# MCU.net
KiCad netlist of a schematic drawn in Altium Designer
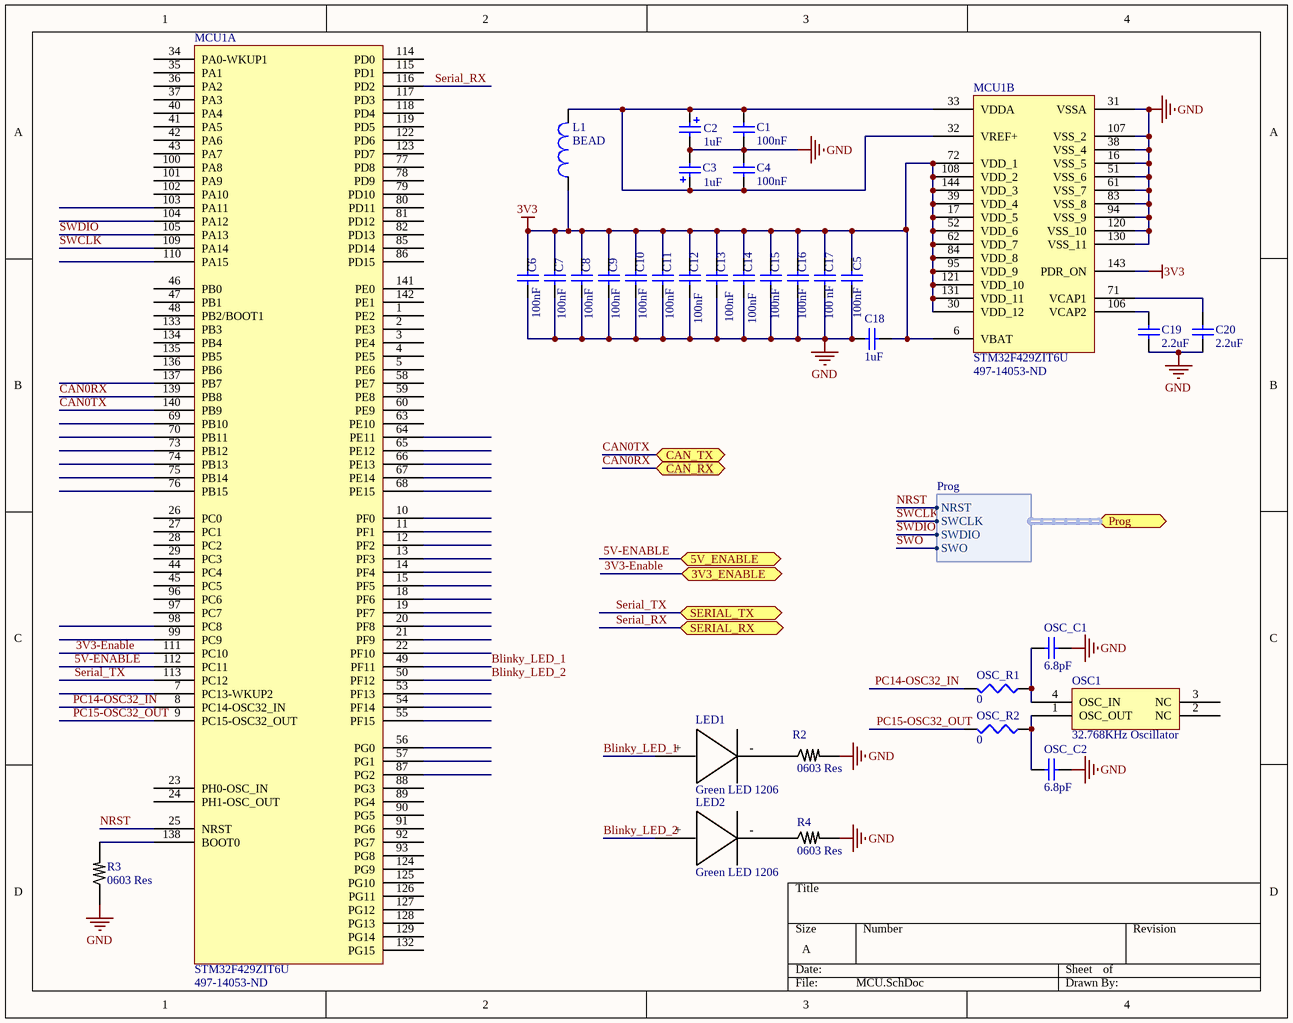
[diagram p0: MCU.SchDoc]

(export (version "E")
  (design (tool "Eeschema 10.0.6"))
  (components
    (comp (ref "C1")
      (value "100nF")
      (footprint "SMD0603")
      (description "Ceramic Chip Capacitor")
      (fields (field (name "Comment") "Cap"))
      (libsource (lib "Components") (part "Capacitor Ceramic"))
    )
    (comp (ref "C2")
      (value "1uF")
      (footprint "SMD1206 Polarized")
      (description "Polarized Capacitor (Surface Mount)")
      (fields (field (name "Comment") "Cap"))
      (libsource (lib "Components") (part "Capacitor Polarized"))
    )
    (comp (ref "C3")
      (value "1uF")
      (footprint "SMD1206 Polarized")
      (description "Polarized Capacitor (Surface Mount)")
      (fields (field (name "Comment") "Cap"))
      (libsource (lib "Components") (part "Capacitor Polarized"))
    )
    (comp (ref "C4")
      (value "100nF")
      (footprint "SMD0603")
      (description "Ceramic Chip Capacitor")
      (fields (field (name "Comment") "Cap"))
      (libsource (lib "Components") (part "Capacitor Ceramic"))
    )
    (comp (ref "C5")
      (value "100nF")
      (footprint "SMD0603")
      (description "Ceramic Chip Capacitor")
      (fields (field (name "Comment") "Cap"))
      (libsource (lib "Components") (part "Capacitor Ceramic"))
    )
    (comp (ref "C6")
      (value "100nF")
      (footprint "SMD0603")
      (description "Ceramic Chip Capacitor")
      (fields (field (name "Comment") "Cap"))
      (libsource (lib "Components") (part "Capacitor Ceramic"))
    )
    (comp (ref "C7")
      (value "100nF")
      (footprint "SMD0603")
      (description "Ceramic Chip Capacitor")
      (fields (field (name "Comment") "Cap"))
      (libsource (lib "Components") (part "Capacitor Ceramic"))
    )
    (comp (ref "C8")
      (value "100nF")
      (footprint "SMD0603")
      (description "Ceramic Chip Capacitor")
      (fields (field (name "Comment") "Cap"))
      (libsource (lib "Components") (part "Capacitor Ceramic"))
    )
    (comp (ref "C9")
      (value "100nF")
      (footprint "SMD0603")
      (description "Ceramic Chip Capacitor")
      (fields (field (name "Comment") "Cap"))
      (libsource (lib "Components") (part "Capacitor Ceramic"))
    )
    (comp (ref "C10")
      (value "100nF")
      (footprint "SMD0603")
      (description "Ceramic Chip Capacitor")
      (fields (field (name "Comment") "Cap"))
      (libsource (lib "Components") (part "Capacitor Ceramic"))
    )
    (comp (ref "C11")
      (value "100nF")
      (footprint "SMD0603")
      (description "Ceramic Chip Capacitor")
      (fields (field (name "Comment") "Cap"))
      (libsource (lib "Components") (part "Capacitor Ceramic"))
    )
    (comp (ref "C12")
      (value "100nF")
      (footprint "SMD0603")
      (description "Ceramic Chip Capacitor")
      (fields (field (name "Comment") "Cap"))
      (libsource (lib "Components") (part "Capacitor Ceramic"))
    )
    (comp (ref "C13")
      (value "100nF")
      (footprint "SMD0603")
      (description "Ceramic Chip Capacitor")
      (fields (field (name "Comment") "Cap"))
      (libsource (lib "Components") (part "Capacitor Ceramic"))
    )
    (comp (ref "C14")
      (value "100nF")
      (footprint "SMD0603")
      (description "Ceramic Chip Capacitor")
      (fields (field (name "Comment") "Cap"))
      (libsource (lib "Components") (part "Capacitor Ceramic"))
    )
    (comp (ref "C15")
      (value "100nF")
      (footprint "SMD0603")
      (description "Ceramic Chip Capacitor")
      (fields (field (name "Comment") "Cap"))
      (libsource (lib "Components") (part "Capacitor Ceramic"))
    )
    (comp (ref "C16")
      (value "100nF")
      (footprint "SMD0603")
      (description "Ceramic Chip Capacitor")
      (fields (field (name "Comment") "Cap"))
      (libsource (lib "Components") (part "Capacitor Ceramic"))
    )
    (comp (ref "C17")
      (value "100 nF")
      (footprint "SMD0603")
      (description "Ceramic Chip Capacitor")
      (fields (field (name "Comment") "Cap"))
      (libsource (lib "Components") (part "Capacitor Ceramic"))
    )
    (comp (ref "C18")
      (value "1uF")
      (footprint "SMD0603")
      (description "Ceramic Chip Capacitor")
      (fields (field (name "Comment") "Cap"))
      (libsource (lib "Components") (part "Capacitor Ceramic"))
    )
    (comp (ref "C19")
      (value "2.2uF")
      (footprint "SMD1206")
      (description "Ceramic Chip Capacitor")
      (fields (field (name "Comment") "Cap"))
      (libsource (lib "Components") (part "Capacitor Ceramic"))
    )
    (comp (ref "C20")
      (value "2.2uF")
      (footprint "SMD1206")
      (description "Ceramic Chip Capacitor")
      (fields (field (name "Comment") "Cap"))
      (libsource (lib "Components") (part "Capacitor Ceramic"))
    )
    (comp (ref "L1")
      (value "BEAD")
      (footprint "SMD0603")
      (description "Ferrite Bead")
      (fields (field (name "PART") "BK1608HS601-TV"))
      (libsource (lib "Components") (part "Chip Ferrite Bead"))
    )
    (comp (ref "LED1")
      (value "Green LED 1206")
      (footprint "Panel_Mount_LED")
      (description "Green surface mount LED")
      (libsource (lib "CUBAJA") (part "1206 Green LED"))
    )
    (comp (ref "LED2")
      (value "Green LED 1206")
      (footprint "Panel_Mount_LED")
      (description "Green surface mount LED")
      (libsource (lib "CUBAJA") (part "1206 Green LED"))
    )
    (comp (ref "MCU1")
      (value "STM32F429ZIT6U")
      (footprint "LQPF144")
      (fields (field (name "SUPPLIER PART NUMBER 1") "497-14053-ND"))
      (libsource (lib "Components") (part "STM32F429ZIT6U"))
    )
    (comp (ref "OSC1")
      (value "32.768KHz Oscillator")
      (footprint "MC-306-OSC")
      (description "32.7680kHz Oscillator")
      (libsource (lib "Components") (part "MC-306 32.768K-E3"))
    )
    (comp (ref "OSC_C1")
      (value "6.8pF")
      (footprint "SMD0603")
      (description "Ceramic Chip Capacitor")
      (fields (field (name "Comment") "Cap"))
      (libsource (lib "Components") (part "Capacitor Ceramic"))
    )
    (comp (ref "OSC_C2")
      (value "6.8pF")
      (footprint "SMD0603")
      (description "Ceramic Chip Capacitor")
      (fields (field (name "Comment") "Cap"))
      (libsource (lib "Components") (part "Capacitor Ceramic"))
    )
    (comp (ref "OSC_R1")
      (value "0")
      (footprint "SMD0603")
      (description "Resistor")
      (fields (field (name "Comment") "Res"))
      (libsource (lib "Components") (part "Resistor"))
    )
    (comp (ref "OSC_R2")
      (value "0")
      (footprint "SMD0603")
      (description "Resistor")
      (fields (field (name "Comment") "Res"))
      (libsource (lib "Components") (part "Resistor"))
    )
    (comp (ref "R2")
      (value "0603 Res")
      (footprint "0603/1608 SMD Resistor")
      (libsource (lib "CornellBajaLibrary") (part "0603 Res"))
    )
    (comp (ref "R3")
      (value "0603 Res")
      (footprint "0603/1608 SMD Resistor")
      (libsource (lib "CornellBajaLibrary") (part "0603 Res"))
    )
    (comp (ref "R4")
      (value "0603 Res")
      (footprint "0603/1608 SMD Resistor")
      (libsource (lib "CornellBajaLibrary") (part "0603 Res"))
    )
  )
  (nets
    (net (code "2") (name "/3V3-Enable") (class "Default")
      (node (ref "MCU1") (pin "111") (pinfunction "PC10_111") (pintype "passive"))
    )
    (net (code "3") (name "/5V-ENABLE") (class "Default")
      (node (ref "MCU1") (pin "112") (pinfunction "PC11_112") (pintype "passive"))
    )
    (net (code "4") (name "/Blinky_LED_1") (class "Default")
      (node (ref "LED1") (pin "+") (pintype "passive"))
      (node (ref "MCU1") (pin "49") (pinfunction "PF11_49") (pintype "passive"))
    )
    (net (code "5") (name "/Blinky_LED_2") (class "Default")
      (node (ref "LED2") (pin "+") (pintype "passive"))
      (node (ref "MCU1") (pin "50") (pinfunction "PF12_50") (pintype "passive"))
    )
    (net (code "6") (name "/CAN0RX") (class "Default")
      (node (ref "MCU1") (pin "139") (pinfunction "PB8_139") (pintype "passive"))
    )
    (net (code "7") (name "/CAN0TX") (class "Default")
      (node (ref "MCU1") (pin "140") (pinfunction "PB9_140") (pintype "passive"))
    )
    (net (code "8") (name "/NRST") (class "Default")
      (node (ref "MCU1") (pin "25") (pinfunction "NRST_25") (pintype "passive"))
    )
    (net (code "9") (name "/PC14-OSC32_IN") (class "Default")
      (node (ref "MCU1") (pin "8") (pinfunction "PC14-OSC32_IN_8") (pintype "passive"))
      (node (ref "OSC_R1") (pin "2") (pinfunction "2_2") (pintype "passive"))
    )
    (net (code "10") (name "/PC15-OSC32_OUT") (class "Default")
      (node (ref "MCU1") (pin "9") (pinfunction "PC15-OSC32_OUT_9") (pintype "passive"))
      (node (ref "OSC_R2") (pin "2") (pinfunction "2_2") (pintype "passive"))
    )
    (net (code "11") (name "/SWCLK") (class "Default")
      (node (ref "MCU1") (pin "109") (pinfunction "PA14_109") (pintype "passive"))
    )
    (net (code "12") (name "/SWDIO") (class "Default")
      (node (ref "MCU1") (pin "105") (pinfunction "PA13_105") (pintype "passive"))
    )
    (net (code "14") (name "/Serial_RX") (class "Default")
      (node (ref "MCU1") (pin "116") (pinfunction "PD2_116") (pintype "passive"))
    )
    (net (code "15") (name "/Serial_TX") (class "Default")
      (node (ref "MCU1") (pin "113") (pinfunction "PC12_113") (pintype "passive"))
    )
    (net (code "17") (name "3V3") (class "Default")
      (node (ref "C10") (pin "2") (pinfunction "2_2") (pintype "passive"))
      (node (ref "C11") (pin "2") (pinfunction "2_2") (pintype "passive"))
      (node (ref "C12") (pin "2") (pinfunction "2_2") (pintype "passive"))
      (node (ref "C13") (pin "2") (pinfunction "2_2") (pintype "passive"))
      (node (ref "C14") (pin "2") (pinfunction "2_2") (pintype "passive"))
      (node (ref "C15") (pin "2") (pinfunction "2_2") (pintype "passive"))
      (node (ref "C16") (pin "2") (pinfunction "2_2") (pintype "passive"))
      (node (ref "C17") (pin "2") (pinfunction "2_2") (pintype "passive"))
      (node (ref "C18") (pin "1") (pinfunction "1_1") (pintype "passive"))
      (node (ref "C5") (pin "1") (pinfunction "1_1") (pintype "passive"))
      (node (ref "C6") (pin "2") (pinfunction "2_2") (pintype "passive"))
      (node (ref "C7") (pin "2") (pinfunction "2_2") (pintype "passive"))
      (node (ref "C8") (pin "2") (pinfunction "2_2") (pintype "passive"))
      (node (ref "C9") (pin "2") (pinfunction "2_2") (pintype "passive"))
      (node (ref "L1") (pin "1") (pintype "passive"))
      (node (ref "MCU1") (pin "108") (pinfunction "VDD_2_108") (pintype "passive"))
      (node (ref "MCU1") (pin "121") (pinfunction "VDD_10_121") (pintype "passive"))
      (node (ref "MCU1") (pin "131") (pinfunction "VDD_11_131") (pintype "passive"))
      (node (ref "MCU1") (pin "143") (pinfunction "PDR_ON_143") (pintype "passive"))
      (node (ref "MCU1") (pin "144") (pinfunction "VDD_3_144") (pintype "passive"))
      (node (ref "MCU1") (pin "17") (pinfunction "VDD_5_17") (pintype "passive"))
      (node (ref "MCU1") (pin "30") (pinfunction "VDD_12_30") (pintype "passive"))
      (node (ref "MCU1") (pin "39") (pinfunction "VDD_4_39") (pintype "passive"))
      (node (ref "MCU1") (pin "52") (pinfunction "VDD_6_52") (pintype "passive"))
      (node (ref "MCU1") (pin "6") (pinfunction "VBAT_6") (pintype "passive"))
      (node (ref "MCU1") (pin "62") (pinfunction "VDD_7_62") (pintype "passive"))
      (node (ref "MCU1") (pin "72") (pinfunction "VDD_1_72") (pintype "passive"))
      (node (ref "MCU1") (pin "84") (pinfunction "VDD_8_84") (pintype "passive"))
      (node (ref "MCU1") (pin "95") (pinfunction "VDD_9_95") (pintype "passive"))
    )
    (net (code "18") (name "GND") (class "Default")
      (node (ref "C1") (pin "1") (pinfunction "1_1") (pintype "passive"))
      (node (ref "C10") (pin "1") (pinfunction "1_1") (pintype "passive"))
      (node (ref "C11") (pin "1") (pinfunction "1_1") (pintype "passive"))
      (node (ref "C12") (pin "1") (pinfunction "1_1") (pintype "passive"))
      (node (ref "C13") (pin "1") (pinfunction "1_1") (pintype "passive"))
      (node (ref "C14") (pin "1") (pinfunction "1_1") (pintype "passive"))
      (node (ref "C15") (pin "1") (pinfunction "1_1") (pintype "passive"))
      (node (ref "C16") (pin "1") (pinfunction "1_1") (pintype "passive"))
      (node (ref "C17") (pin "1") (pinfunction "1_1") (pintype "passive"))
      (node (ref "C18") (pin "2") (pinfunction "2_2") (pintype "passive"))
      (node (ref "C19") (pin "1") (pinfunction "1_1") (pintype "passive"))
      (node (ref "C2") (pin "2") (pinfunction "2_2") (pintype "passive"))
      (node (ref "C20") (pin "1") (pinfunction "1_1") (pintype "passive"))
      (node (ref "C3") (pin "2") (pinfunction "2_2") (pintype "passive"))
      (node (ref "C4") (pin "2") (pinfunction "2_2") (pintype "passive"))
      (node (ref "C5") (pin "2") (pinfunction "2_2") (pintype "passive"))
      (node (ref "C6") (pin "1") (pinfunction "1_1") (pintype "passive"))
      (node (ref "C7") (pin "1") (pinfunction "1_1") (pintype "passive"))
      (node (ref "C8") (pin "1") (pinfunction "1_1") (pintype "passive"))
      (node (ref "C9") (pin "1") (pinfunction "1_1") (pintype "passive"))
      (node (ref "MCU1") (pin "107") (pinfunction "VSS_2_107") (pintype "passive"))
      (node (ref "MCU1") (pin "120") (pinfunction "VSS_10_120") (pintype "passive"))
      (node (ref "MCU1") (pin "130") (pinfunction "VSS_11_130") (pintype "passive"))
      (node (ref "MCU1") (pin "16") (pinfunction "VSS_5_16") (pintype "passive"))
      (node (ref "MCU1") (pin "31") (pinfunction "VSSA_31") (pintype "passive"))
      (node (ref "MCU1") (pin "38") (pinfunction "VSS_4_38") (pintype "passive"))
      (node (ref "MCU1") (pin "51") (pinfunction "VSS_6_51") (pintype "passive"))
      (node (ref "MCU1") (pin "61") (pinfunction "VSS_7_61") (pintype "passive"))
      (node (ref "MCU1") (pin "83") (pinfunction "VSS_8_83") (pintype "passive"))
      (node (ref "MCU1") (pin "94") (pinfunction "VSS_9_94") (pintype "passive"))
      (node (ref "OSC_C1") (pin "1") (pinfunction "1_1") (pintype "passive"))
      (node (ref "OSC_C2") (pin "1") (pinfunction "1_1") (pintype "passive"))
      (node (ref "R2") (pin "2") (pinfunction "2_2") (pintype "passive"))
      (node (ref "R3") (pin "1") (pinfunction "1_1") (pintype "passive"))
      (node (ref "R4") (pin "2") (pinfunction "2_2") (pintype "passive"))
    )
    (net (code "19") (name "Net-(LED1-Pad-)") (class "Default")
      (node (ref "LED1") (pin "-") (pintype "passive"))
      (node (ref "R2") (pin "1") (pinfunction "1_1") (pintype "passive"))
    )
    (net (code "20") (name "Net-(LED2-Pad-)") (class "Default")
      (node (ref "LED2") (pin "-") (pintype "passive"))
      (node (ref "R4") (pin "1") (pinfunction "1_1") (pintype "passive"))
    )
    (net (code "21") (name "Net-(MCU1A-BOOT0)") (class "Default")
      (node (ref "MCU1") (pin "138") (pinfunction "BOOT0_138") (pintype "passive"))
      (node (ref "R3") (pin "2") (pinfunction "2_2") (pintype "passive"))
    )
    (net (code "22") (name "Net-(MCU1B-VCAP1)") (class "Default")
      (node (ref "C20") (pin "2") (pinfunction "2_2") (pintype "passive"))
      (node (ref "MCU1") (pin "71") (pinfunction "VCAP1_71") (pintype "passive"))
    )
    (net (code "23") (name "Net-(MCU1B-VCAP2)") (class "Default")
      (node (ref "C19") (pin "2") (pinfunction "2_2") (pintype "passive"))
      (node (ref "MCU1") (pin "106") (pinfunction "VCAP2_106") (pintype "passive"))
    )
    (net (code "24") (name "Net-(MCU1B-VDDA)") (class "Default")
      (node (ref "C1") (pin "2") (pinfunction "2_2") (pintype "passive"))
      (node (ref "C2") (pin "1") (pinfunction "1_1") (pintype "passive"))
      (node (ref "C3") (pin "1") (pinfunction "1_1") (pintype "passive"))
      (node (ref "C4") (pin "1") (pinfunction "1_1") (pintype "passive"))
      (node (ref "L1") (pin "2") (pintype "passive"))
      (node (ref "MCU1") (pin "32") (pinfunction "VREF+_32") (pintype "passive"))
      (node (ref "MCU1") (pin "33") (pinfunction "VDDA_33") (pintype "passive"))
    )
    (net (code "25") (name "Net-(OSC1-OSC_IN)") (class "Default")
      (node (ref "OSC1") (pin "4") (pinfunction "OSC_IN_4") (pintype "passive"))
      (node (ref "OSC_C1") (pin "2") (pinfunction "2_2") (pintype "passive"))
      (node (ref "OSC_R1") (pin "1") (pinfunction "1_1") (pintype "passive"))
    )
    (net (code "26") (name "Net-(OSC1-OSC_OUT)") (class "Default")
      (node (ref "OSC1") (pin "1") (pinfunction "OSC_OUT_1") (pintype "passive"))
      (node (ref "OSC_C2") (pin "2") (pinfunction "2_2") (pintype "passive"))
      (node (ref "OSC_R2") (pin "1") (pinfunction "1_1") (pintype "passive"))
    )
    (net (code "27") (name "unconnected-(MCU1A-PA0-WKUP1-Pad34)") (class "Default")
      (node (ref "MCU1") (pin "34") (pinfunction "PA0-WKUP1_34") (pintype "passive"))
    )
    (net (code "28") (name "unconnected-(MCU1A-PA1-Pad35)") (class "Default")
      (node (ref "MCU1") (pin "35") (pinfunction "PA1_35") (pintype "passive"))
    )
    (net (code "29") (name "unconnected-(MCU1A-PA2-Pad36)") (class "Default")
      (node (ref "MCU1") (pin "36") (pinfunction "PA2_36") (pintype "passive"))
    )
    (net (code "30") (name "unconnected-(MCU1A-PA3-Pad37)") (class "Default")
      (node (ref "MCU1") (pin "37") (pinfunction "PA3_37") (pintype "passive"))
    )
    (net (code "31") (name "unconnected-(MCU1A-PA4-Pad40)") (class "Default")
      (node (ref "MCU1") (pin "40") (pinfunction "PA4_40") (pintype "passive"))
    )
    (net (code "32") (name "unconnected-(MCU1A-PA5-Pad41)") (class "Default")
      (node (ref "MCU1") (pin "41") (pinfunction "PA5_41") (pintype "passive"))
    )
    (net (code "33") (name "unconnected-(MCU1A-PA6-Pad42)") (class "Default")
      (node (ref "MCU1") (pin "42") (pinfunction "PA6_42") (pintype "passive"))
    )
    (net (code "34") (name "unconnected-(MCU1A-PA7-Pad43)") (class "Default")
      (node (ref "MCU1") (pin "43") (pinfunction "PA7_43") (pintype "passive"))
    )
    (net (code "35") (name "unconnected-(MCU1A-PA8-Pad100)") (class "Default")
      (node (ref "MCU1") (pin "100") (pinfunction "PA8_100") (pintype "passive"))
    )
    (net (code "36") (name "unconnected-(MCU1A-PA9-Pad101)") (class "Default")
      (node (ref "MCU1") (pin "101") (pinfunction "PA9_101") (pintype "passive"))
    )
    (net (code "37") (name "unconnected-(MCU1A-PA10-Pad102)") (class "Default")
      (node (ref "MCU1") (pin "102") (pinfunction "PA10_102") (pintype "passive"))
    )
    (net (code "38") (name "unconnected-(MCU1A-PA11-Pad103)") (class "Default")
      (node (ref "MCU1") (pin "103") (pinfunction "PA11_103") (pintype "passive"))
    )
    (net (code "39") (name "unconnected-(MCU1A-PA12-Pad104)") (class "Default")
      (node (ref "MCU1") (pin "104") (pinfunction "PA12_104") (pintype "passive"))
    )
    (net (code "40") (name "unconnected-(MCU1A-PA15-Pad110)") (class "Default")
      (node (ref "MCU1") (pin "110") (pinfunction "PA15_110") (pintype "passive"))
    )
    (net (code "41") (name "unconnected-(MCU1A-PB0-Pad46)") (class "Default")
      (node (ref "MCU1") (pin "46") (pinfunction "PB0_46") (pintype "passive"))
    )
    (net (code "42") (name "unconnected-(MCU1A-PB1-Pad47)") (class "Default")
      (node (ref "MCU1") (pin "47") (pinfunction "PB1_47") (pintype "passive"))
    )
    (net (code "43") (name "unconnected-(MCU1A-PB2{slash}BOOT1-Pad48)") (class "Default")
      (node (ref "MCU1") (pin "48") (pinfunction "PB2/BOOT1_48") (pintype "passive"))
    )
    (net (code "44") (name "unconnected-(MCU1A-PB3-Pad133)") (class "Default")
      (node (ref "MCU1") (pin "133") (pinfunction "PB3_133") (pintype "passive"))
    )
    (net (code "45") (name "unconnected-(MCU1A-PB4-Pad134)") (class "Default")
      (node (ref "MCU1") (pin "134") (pinfunction "PB4_134") (pintype "passive"))
    )
    (net (code "46") (name "unconnected-(MCU1A-PB5-Pad135)") (class "Default")
      (node (ref "MCU1") (pin "135") (pinfunction "PB5_135") (pintype "passive"))
    )
    (net (code "47") (name "unconnected-(MCU1A-PB6-Pad136)") (class "Default")
      (node (ref "MCU1") (pin "136") (pinfunction "PB6_136") (pintype "passive"))
    )
    (net (code "48") (name "unconnected-(MCU1A-PB7-Pad137)") (class "Default")
      (node (ref "MCU1") (pin "137") (pinfunction "PB7_137") (pintype "passive"))
    )
    (net (code "49") (name "unconnected-(MCU1A-PB10-Pad69)") (class "Default")
      (node (ref "MCU1") (pin "69") (pinfunction "PB10_69") (pintype "passive"))
    )
    (net (code "50") (name "unconnected-(MCU1A-PB11-Pad70)") (class "Default")
      (node (ref "MCU1") (pin "70") (pinfunction "PB11_70") (pintype "passive"))
    )
    (net (code "51") (name "unconnected-(MCU1A-PB12-Pad73)") (class "Default")
      (node (ref "MCU1") (pin "73") (pinfunction "PB12_73") (pintype "passive"))
    )
    (net (code "52") (name "unconnected-(MCU1A-PB13-Pad74)") (class "Default")
      (node (ref "MCU1") (pin "74") (pinfunction "PB13_74") (pintype "passive"))
    )
    (net (code "53") (name "unconnected-(MCU1A-PB14-Pad75)") (class "Default")
      (node (ref "MCU1") (pin "75") (pinfunction "PB14_75") (pintype "passive"))
    )
    (net (code "54") (name "unconnected-(MCU1A-PB15-Pad76)") (class "Default")
      (node (ref "MCU1") (pin "76") (pinfunction "PB15_76") (pintype "passive"))
    )
    (net (code "55") (name "unconnected-(MCU1A-PC0-Pad26)") (class "Default")
      (node (ref "MCU1") (pin "26") (pinfunction "PC0_26") (pintype "passive"))
    )
    (net (code "56") (name "unconnected-(MCU1A-PC1-Pad27)") (class "Default")
      (node (ref "MCU1") (pin "27") (pinfunction "PC1_27") (pintype "passive"))
    )
    (net (code "57") (name "unconnected-(MCU1A-PC2-Pad28)") (class "Default")
      (node (ref "MCU1") (pin "28") (pinfunction "PC2_28") (pintype "passive"))
    )
    (net (code "58") (name "unconnected-(MCU1A-PC3-Pad29)") (class "Default")
      (node (ref "MCU1") (pin "29") (pinfunction "PC3_29") (pintype "passive"))
    )
    (net (code "59") (name "unconnected-(MCU1A-PC4-Pad44)") (class "Default")
      (node (ref "MCU1") (pin "44") (pinfunction "PC4_44") (pintype "passive"))
    )
    (net (code "60") (name "unconnected-(MCU1A-PC5-Pad45)") (class "Default")
      (node (ref "MCU1") (pin "45") (pinfunction "PC5_45") (pintype "passive"))
    )
    (net (code "61") (name "unconnected-(MCU1A-PC6-Pad96)") (class "Default")
      (node (ref "MCU1") (pin "96") (pinfunction "PC6_96") (pintype "passive"))
    )
    (net (code "62") (name "unconnected-(MCU1A-PC7-Pad97)") (class "Default")
      (node (ref "MCU1") (pin "97") (pinfunction "PC7_97") (pintype "passive"))
    )
    (net (code "63") (name "unconnected-(MCU1A-PC8-Pad98)") (class "Default")
      (node (ref "MCU1") (pin "98") (pinfunction "PC8_98") (pintype "passive"))
    )
    (net (code "64") (name "unconnected-(MCU1A-PC9-Pad99)") (class "Default")
      (node (ref "MCU1") (pin "99") (pinfunction "PC9_99") (pintype "passive"))
    )
    (net (code "65") (name "unconnected-(MCU1A-PC13-WKUP2-Pad7)") (class "Default")
      (node (ref "MCU1") (pin "7") (pinfunction "PC13-WKUP2_7") (pintype "passive"))
    )
    (net (code "66") (name "unconnected-(MCU1A-PD0-Pad114)") (class "Default")
      (node (ref "MCU1") (pin "114") (pinfunction "PD0_114") (pintype "passive"))
    )
    (net (code "67") (name "unconnected-(MCU1A-PD1-Pad115)") (class "Default")
      (node (ref "MCU1") (pin "115") (pinfunction "PD1_115") (pintype "passive"))
    )
    (net (code "68") (name "unconnected-(MCU1A-PD3-Pad117)") (class "Default")
      (node (ref "MCU1") (pin "117") (pinfunction "PD3_117") (pintype "passive"))
    )
    (net (code "69") (name "unconnected-(MCU1A-PD4-Pad118)") (class "Default")
      (node (ref "MCU1") (pin "118") (pinfunction "PD4_118") (pintype "passive"))
    )
    (net (code "70") (name "unconnected-(MCU1A-PD5-Pad119)") (class "Default")
      (node (ref "MCU1") (pin "119") (pinfunction "PD5_119") (pintype "passive"))
    )
    (net (code "71") (name "unconnected-(MCU1A-PD6-Pad122)") (class "Default")
      (node (ref "MCU1") (pin "122") (pinfunction "PD6_122") (pintype "passive"))
    )
    (net (code "72") (name "unconnected-(MCU1A-PD7-Pad123)") (class "Default")
      (node (ref "MCU1") (pin "123") (pinfunction "PD7_123") (pintype "passive"))
    )
    (net (code "73") (name "unconnected-(MCU1A-PD8-Pad77)") (class "Default")
      (node (ref "MCU1") (pin "77") (pinfunction "PD8_77") (pintype "passive"))
    )
    (net (code "74") (name "unconnected-(MCU1A-PD9-Pad78)") (class "Default")
      (node (ref "MCU1") (pin "78") (pinfunction "PD9_78") (pintype "passive"))
    )
    (net (code "75") (name "unconnected-(MCU1A-PD10-Pad79)") (class "Default")
      (node (ref "MCU1") (pin "79") (pinfunction "PD10_79") (pintype "passive"))
    )
    (net (code "76") (name "unconnected-(MCU1A-PD11-Pad80)") (class "Default")
      (node (ref "MCU1") (pin "80") (pinfunction "PD11_80") (pintype "passive"))
    )
    (net (code "77") (name "unconnected-(MCU1A-PD12-Pad81)") (class "Default")
      (node (ref "MCU1") (pin "81") (pinfunction "PD12_81") (pintype "passive"))
    )
    (net (code "78") (name "unconnected-(MCU1A-PD13-Pad82)") (class "Default")
      (node (ref "MCU1") (pin "82") (pinfunction "PD13_82") (pintype "passive"))
    )
    (net (code "79") (name "unconnected-(MCU1A-PD14-Pad85)") (class "Default")
      (node (ref "MCU1") (pin "85") (pinfunction "PD14_85") (pintype "passive"))
    )
    (net (code "80") (name "unconnected-(MCU1A-PD15-Pad86)") (class "Default")
      (node (ref "MCU1") (pin "86") (pinfunction "PD15_86") (pintype "passive"))
    )
    (net (code "81") (name "unconnected-(MCU1A-PE0-Pad141)") (class "Default")
      (node (ref "MCU1") (pin "141") (pinfunction "PE0_141") (pintype "passive"))
    )
    (net (code "82") (name "unconnected-(MCU1A-PE1-Pad142)") (class "Default")
      (node (ref "MCU1") (pin "142") (pinfunction "PE1_142") (pintype "passive"))
    )
    (net (code "83") (name "unconnected-(MCU1A-PE2-Pad1)") (class "Default")
      (node (ref "MCU1") (pin "1") (pinfunction "PE2_1") (pintype "passive"))
    )
    (net (code "84") (name "unconnected-(MCU1A-PE3-Pad2)") (class "Default")
      (node (ref "MCU1") (pin "2") (pinfunction "PE3_2") (pintype "passive"))
    )
    (net (code "85") (name "unconnected-(MCU1A-PE4-Pad3)") (class "Default")
      (node (ref "MCU1") (pin "3") (pinfunction "PE4_3") (pintype "passive"))
    )
    (net (code "86") (name "unconnected-(MCU1A-PE5-Pad4)") (class "Default")
      (node (ref "MCU1") (pin "4") (pinfunction "PE5_4") (pintype "passive"))
    )
    (net (code "87") (name "unconnected-(MCU1A-PE6-Pad5)") (class "Default")
      (node (ref "MCU1") (pin "5") (pinfunction "PE6_5") (pintype "passive"))
    )
    (net (code "88") (name "unconnected-(MCU1A-PE7-Pad58)") (class "Default")
      (node (ref "MCU1") (pin "58") (pinfunction "PE7_58") (pintype "passive"))
    )
    (net (code "89") (name "unconnected-(MCU1A-PE8-Pad59)") (class "Default")
      (node (ref "MCU1") (pin "59") (pinfunction "PE8_59") (pintype "passive"))
    )
    (net (code "90") (name "unconnected-(MCU1A-PE9-Pad60)") (class "Default")
      (node (ref "MCU1") (pin "60") (pinfunction "PE9_60") (pintype "passive"))
    )
    (net (code "91") (name "unconnected-(MCU1A-PE10-Pad63)") (class "Default")
      (node (ref "MCU1") (pin "63") (pinfunction "PE10_63") (pintype "passive"))
    )
    (net (code "92") (name "unconnected-(MCU1A-PE11-Pad64)") (class "Default")
      (node (ref "MCU1") (pin "64") (pinfunction "PE11_64") (pintype "passive"))
    )
    (net (code "93") (name "unconnected-(MCU1A-PE12-Pad65)") (class "Default")
      (node (ref "MCU1") (pin "65") (pinfunction "PE12_65") (pintype "passive"))
    )
    (net (code "94") (name "unconnected-(MCU1A-PE13-Pad66)") (class "Default")
      (node (ref "MCU1") (pin "66") (pinfunction "PE13_66") (pintype "passive"))
    )
    (net (code "95") (name "unconnected-(MCU1A-PE14-Pad67)") (class "Default")
      (node (ref "MCU1") (pin "67") (pinfunction "PE14_67") (pintype "passive"))
    )
    (net (code "96") (name "unconnected-(MCU1A-PE15-Pad68)") (class "Default")
      (node (ref "MCU1") (pin "68") (pinfunction "PE15_68") (pintype "passive"))
    )
    (net (code "97") (name "unconnected-(MCU1A-PF0-Pad10)") (class "Default")
      (node (ref "MCU1") (pin "10") (pinfunction "PF0_10") (pintype "passive"))
    )
    (net (code "98") (name "unconnected-(MCU1A-PF1-Pad11)") (class "Default")
      (node (ref "MCU1") (pin "11") (pinfunction "PF1_11") (pintype "passive"))
    )
    (net (code "99") (name "unconnected-(MCU1A-PF2-Pad12)") (class "Default")
      (node (ref "MCU1") (pin "12") (pinfunction "PF2_12") (pintype "passive"))
    )
    (net (code "100") (name "unconnected-(MCU1A-PF3-Pad13)") (class "Default")
      (node (ref "MCU1") (pin "13") (pinfunction "PF3_13") (pintype "passive"))
    )
    (net (code "101") (name "unconnected-(MCU1A-PF4-Pad14)") (class "Default")
      (node (ref "MCU1") (pin "14") (pinfunction "PF4_14") (pintype "passive"))
    )
    (net (code "102") (name "unconnected-(MCU1A-PF5-Pad15)") (class "Default")
      (node (ref "MCU1") (pin "15") (pinfunction "PF5_15") (pintype "passive"))
    )
    (net (code "103") (name "unconnected-(MCU1A-PF6-Pad18)") (class "Default")
      (node (ref "MCU1") (pin "18") (pinfunction "PF6_18") (pintype "passive"))
    )
    (net (code "104") (name "unconnected-(MCU1A-PF7-Pad19)") (class "Default")
      (node (ref "MCU1") (pin "19") (pinfunction "PF7_19") (pintype "passive"))
    )
    (net (code "105") (name "unconnected-(MCU1A-PF8-Pad20)") (class "Default")
      (node (ref "MCU1") (pin "20") (pinfunction "PF8_20") (pintype "passive"))
    )
    (net (code "106") (name "unconnected-(MCU1A-PF9-Pad21)") (class "Default")
      (node (ref "MCU1") (pin "21") (pinfunction "PF9_21") (pintype "passive"))
    )
    (net (code "107") (name "unconnected-(MCU1A-PF10-Pad22)") (class "Default")
      (node (ref "MCU1") (pin "22") (pinfunction "PF10_22") (pintype "passive"))
    )
    (net (code "108") (name "unconnected-(MCU1A-PF13-Pad53)") (class "Default")
      (node (ref "MCU1") (pin "53") (pinfunction "PF13_53") (pintype "passive"))
    )
    (net (code "109") (name "unconnected-(MCU1A-PF14-Pad54)") (class "Default")
      (node (ref "MCU1") (pin "54") (pinfunction "PF14_54") (pintype "passive"))
    )
    (net (code "110") (name "unconnected-(MCU1A-PF15-Pad55)") (class "Default")
      (node (ref "MCU1") (pin "55") (pinfunction "PF15_55") (pintype "passive"))
    )
    (net (code "111") (name "unconnected-(MCU1A-PG0-Pad56)") (class "Default")
      (node (ref "MCU1") (pin "56") (pinfunction "PG0_56") (pintype "passive"))
    )
    (net (code "112") (name "unconnected-(MCU1A-PG1-Pad57)") (class "Default")
      (node (ref "MCU1") (pin "57") (pinfunction "PG1_57") (pintype "passive"))
    )
    (net (code "113") (name "unconnected-(MCU1A-PG2-Pad87)") (class "Default")
      (node (ref "MCU1") (pin "87") (pinfunction "PG2_87") (pintype "passive"))
    )
    (net (code "114") (name "unconnected-(MCU1A-PG3-Pad88)") (class "Default")
      (node (ref "MCU1") (pin "88") (pinfunction "PG3_88") (pintype "passive"))
    )
    (net (code "115") (name "unconnected-(MCU1A-PG4-Pad89)") (class "Default")
      (node (ref "MCU1") (pin "89") (pinfunction "PG4_89") (pintype "passive"))
    )
    (net (code "116") (name "unconnected-(MCU1A-PG5-Pad90)") (class "Default")
      (node (ref "MCU1") (pin "90") (pinfunction "PG5_90") (pintype "passive"))
    )
    (net (code "117") (name "unconnected-(MCU1A-PG6-Pad91)") (class "Default")
      (node (ref "MCU1") (pin "91") (pinfunction "PG6_91") (pintype "passive"))
    )
    (net (code "118") (name "unconnected-(MCU1A-PG7-Pad92)") (class "Default")
      (node (ref "MCU1") (pin "92") (pinfunction "PG7_92") (pintype "passive"))
    )
    (net (code "119") (name "unconnected-(MCU1A-PG8-Pad93)") (class "Default")
      (node (ref "MCU1") (pin "93") (pinfunction "PG8_93") (pintype "passive"))
    )
    (net (code "120") (name "unconnected-(MCU1A-PG9-Pad124)") (class "Default")
      (node (ref "MCU1") (pin "124") (pinfunction "PG9_124") (pintype "passive"))
    )
    (net (code "121") (name "unconnected-(MCU1A-PG10-Pad125)") (class "Default")
      (node (ref "MCU1") (pin "125") (pinfunction "PG10_125") (pintype "passive"))
    )
    (net (code "122") (name "unconnected-(MCU1A-PG11-Pad126)") (class "Default")
      (node (ref "MCU1") (pin "126") (pinfunction "PG11_126") (pintype "passive"))
    )
    (net (code "123") (name "unconnected-(MCU1A-PG12-Pad127)") (class "Default")
      (node (ref "MCU1") (pin "127") (pinfunction "PG12_127") (pintype "passive"))
    )
    (net (code "124") (name "unconnected-(MCU1A-PG13-Pad128)") (class "Default")
      (node (ref "MCU1") (pin "128") (pinfunction "PG13_128") (pintype "passive"))
    )
    (net (code "125") (name "unconnected-(MCU1A-PG14-Pad129)") (class "Default")
      (node (ref "MCU1") (pin "129") (pinfunction "PG14_129") (pintype "passive"))
    )
    (net (code "126") (name "unconnected-(MCU1A-PG15-Pad132)") (class "Default")
      (node (ref "MCU1") (pin "132") (pinfunction "PG15_132") (pintype "passive"))
    )
    (net (code "127") (name "unconnected-(MCU1A-PH0-OSC_IN-Pad23)") (class "Default")
      (node (ref "MCU1") (pin "23") (pinfunction "PH0-OSC_IN_23") (pintype "passive"))
    )
    (net (code "128") (name "unconnected-(MCU1A-PH1-OSC_OUT-Pad24)") (class "Default")
      (node (ref "MCU1") (pin "24") (pinfunction "PH1-OSC_OUT_24") (pintype "passive"))
    )
    (net (code "129") (name "unconnected-(OSC1-NC-Pad2)") (class "Default")
      (node (ref "OSC1") (pin "2") (pinfunction "NC_2") (pintype "passive"))
    )
    (net (code "130") (name "unconnected-(OSC1-NC-Pad3)") (class "Default")
      (node (ref "OSC1") (pin "3") (pinfunction "NC_3") (pintype "passive"))
    )
  )
)
